# Buttons.net
KiCad netlist of a schematic drawn in EAGLE
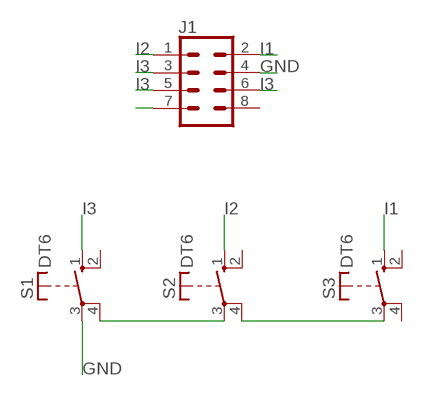
[diagram p0: schematic, sheet 1]

(export (version "E")
  (design (tool "Eeschema 10.0.6"))
  (components
    (comp (ref "J1")
      (value "CONN_04X2")
      (footprint "eagle-import:2X4")
      (libsource (lib "eagle-import") (part "CONN_04X2"))
    )
    (comp (ref "S1")
      (value "DT6")
      (footprint "eagle-import:DT6")
      (libsource (lib "eagle-import") (part "DT6"))
    )
    (comp (ref "S2")
      (value "DT6")
      (footprint "eagle-import:DT6")
      (libsource (lib "eagle-import") (part "DT6"))
    )
    (comp (ref "S3")
      (value "DT6")
      (footprint "eagle-import:DT6")
      (libsource (lib "eagle-import") (part "DT6"))
    )
  )
  (nets
    (net (code "1") (name "/GND") (class "Default")
      (node (ref "J1") (pin "4") (pinfunction "4_4") (pintype "passive"))
      (node (ref "S1") (pin "3") (pinfunction "P_3") (pintype "passive"))
    )
    (net (code "2") (name "/I1") (class "Default")
      (node (ref "J1") (pin "2") (pinfunction "2_2") (pintype "passive"))
      (node (ref "S3") (pin "1") (pinfunction "S_1") (pintype "passive"))
    )
    (net (code "3") (name "/I2") (class "Default")
      (node (ref "J1") (pin "1") (pinfunction "1_1") (pintype "passive"))
      (node (ref "S2") (pin "1") (pinfunction "S_1") (pintype "passive"))
    )
    (net (code "4") (name "/I3") (class "Default")
      (node (ref "J1") (pin "3") (pinfunction "3_3") (pintype "passive"))
      (node (ref "J1") (pin "5") (pinfunction "5_5") (pintype "passive"))
      (node (ref "J1") (pin "6") (pinfunction "6_6") (pintype "passive"))
      (node (ref "S1") (pin "1") (pinfunction "S_1") (pintype "passive"))
    )
    (net (code "5") (name "Net-(S1-P-Pad4)") (class "Default")
      (node (ref "S1") (pin "4") (pinfunction "P_4") (pintype "passive"))
      (node (ref "S2") (pin "3") (pinfunction "P_3") (pintype "passive"))
    )
    (net (code "6") (name "Net-(S2-P-Pad4)") (class "Default")
      (node (ref "S2") (pin "4") (pinfunction "P_4") (pintype "passive"))
      (node (ref "S3") (pin "3") (pinfunction "P_3") (pintype "passive"))
    )
    (net (code "7") (name "unconnected-(J1-Pad7)") (class "Default")
      (node (ref "J1") (pin "7") (pinfunction "7_7") (pintype "passive"))
    )
    (net (code "8") (name "unconnected-(J1-Pad8)") (class "Default")
      (node (ref "J1") (pin "8") (pinfunction "8_8") (pintype "passive"))
    )
    (net (code "9") (name "unconnected-(S1-S-Pad2)") (class "Default")
      (node (ref "S1") (pin "2") (pinfunction "S_2") (pintype "passive"))
    )
    (net (code "10") (name "unconnected-(S2-S-Pad2)") (class "Default")
      (node (ref "S2") (pin "2") (pinfunction "S_2") (pintype "passive"))
    )
    (net (code "11") (name "unconnected-(S3-P-Pad4)") (class "Default")
      (node (ref "S3") (pin "4") (pinfunction "P_4") (pintype "passive"))
    )
    (net (code "12") (name "unconnected-(S3-S-Pad2)") (class "Default")
      (node (ref "S3") (pin "2") (pinfunction "S_2") (pintype "passive"))
    )
  )
)
